# LFO.net
KiCad netlist of a schematic drawn in EAGLE
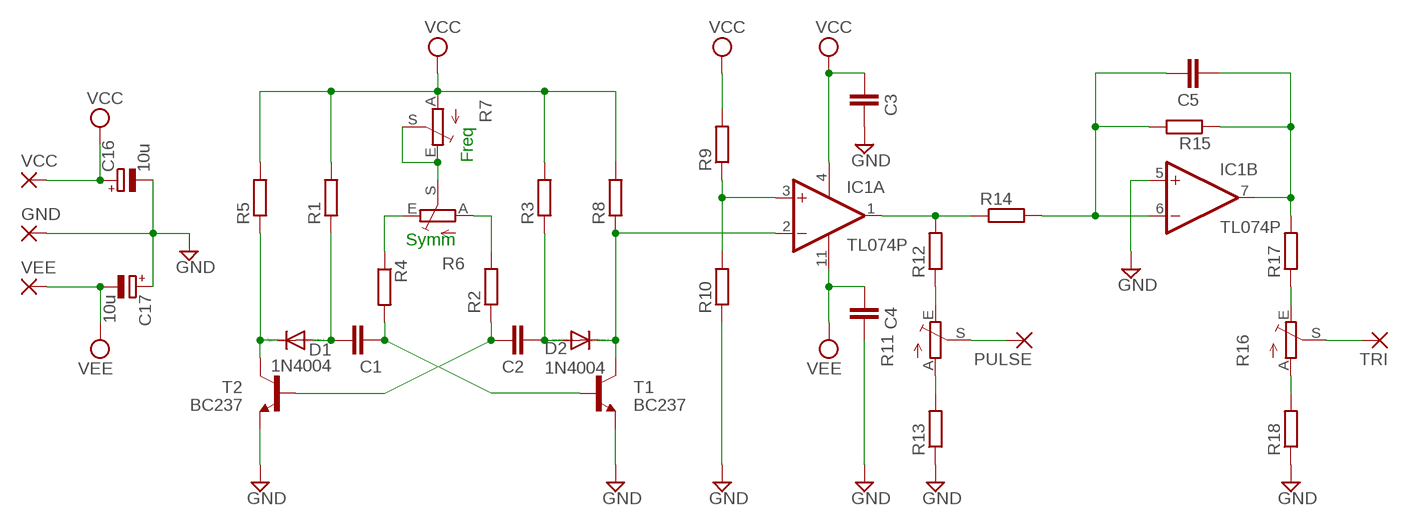
[diagram p0: schematic, sheet 1]

(export (version "E")
  (design (tool "Eeschema 10.0.6"))
  (components
    (comp (ref "C1")
      (value "C-EU050-045X075")
      (footprint "eagle-import:C050-045X075")
      (libsource (lib "eagle-import") (part "C-EU050-045X075"))
    )
    (comp (ref "C2")
      (value "C-EU050-045X075")
      (footprint "eagle-import:C050-045X075")
      (libsource (lib "eagle-import") (part "C-EU050-045X075"))
    )
    (comp (ref "C3")
      (value "C-EU050-045X075")
      (footprint "eagle-import:C050-045X075")
      (libsource (lib "eagle-import") (part "C-EU050-045X075"))
    )
    (comp (ref "C4")
      (value "C-EU050-045X075")
      (footprint "eagle-import:C050-045X075")
      (libsource (lib "eagle-import") (part "C-EU050-045X075"))
    )
    (comp (ref "C5")
      (value "C-EU050-045X075")
      (footprint "eagle-import:C050-045X075")
      (libsource (lib "eagle-import") (part "C-EU050-045X075"))
    )
    (comp (ref "C16")
      (value "10u")
      (footprint "eagle-import:E2,5-7")
      (libsource (lib "eagle-import") (part "CPOL-EUE2.5-7"))
    )
    (comp (ref "C17")
      (value "10u")
      (footprint "eagle-import:E2,5-7")
      (libsource (lib "eagle-import") (part "CPOL-EUE2.5-7"))
    )
    (comp (ref "D1")
      (value "1N4004")
      (footprint "eagle-import:DO41-10")
      (libsource (lib "eagle-import") (part "1N4004"))
    )
    (comp (ref "D2")
      (value "1N4004")
      (footprint "eagle-import:DO41-10")
      (libsource (lib "eagle-import") (part "1N4004"))
    )
    (comp (ref "GND")
      (value "3,17/1,1")
      (footprint "eagle-import:3,17_1,1")
      (libsource (lib "eagle-import") (part "3,17/1,1"))
    )
    (comp (ref "IC1")
      (value "TL074P")
      (footprint "eagle-import:DIL14")
      (libsource (lib "eagle-import") (part "TL074P"))
    )
    (comp (ref "PULSE")
      (value "3,17/1,1")
      (footprint "eagle-import:3,17_1,1")
      (libsource (lib "eagle-import") (part "3,17/1,1"))
    )
    (comp (ref "R1")
      (value "R-EU_0207/10")
      (footprint "eagle-import:0207_10")
      (libsource (lib "eagle-import") (part "R-EU_0207/10"))
    )
    (comp (ref "R2")
      (value "R-EU_0207/10")
      (footprint "eagle-import:0207_10")
      (libsource (lib "eagle-import") (part "R-EU_0207/10"))
    )
    (comp (ref "R3")
      (value "R-EU_0207/10")
      (footprint "eagle-import:0207_10")
      (libsource (lib "eagle-import") (part "R-EU_0207/10"))
    )
    (comp (ref "R4")
      (value "R-EU_0207/10")
      (footprint "eagle-import:0207_10")
      (libsource (lib "eagle-import") (part "R-EU_0207/10"))
    )
    (comp (ref "R5")
      (value "R-EU_0207/10")
      (footprint "eagle-import:0207_10")
      (libsource (lib "eagle-import") (part "R-EU_0207/10"))
    )
    (comp (ref "R6")
      (value "TRIM_EU-S75P")
      (footprint "eagle-import:S75P")
      (libsource (lib "eagle-import") (part "TRIM_EU-S75P"))
    )
    (comp (ref "R7")
      (value "TRIM_EU-S75P")
      (footprint "eagle-import:S75P")
      (libsource (lib "eagle-import") (part "TRIM_EU-S75P"))
    )
    (comp (ref "R8")
      (value "R-EU_0207/10")
      (footprint "eagle-import:0207_10")
      (libsource (lib "eagle-import") (part "R-EU_0207/10"))
    )
    (comp (ref "R9")
      (value "R-EU_0207/10")
      (footprint "eagle-import:0207_10")
      (libsource (lib "eagle-import") (part "R-EU_0207/10"))
    )
    (comp (ref "R10")
      (value "R-EU_0207/10")
      (footprint "eagle-import:0207_10")
      (libsource (lib "eagle-import") (part "R-EU_0207/10"))
    )
    (comp (ref "R11")
      (value "TRIM_EU-S75P")
      (footprint "eagle-import:S75P")
      (libsource (lib "eagle-import") (part "TRIM_EU-S75P"))
    )
    (comp (ref "R12")
      (value "R-EU_0207/10")
      (footprint "eagle-import:0207_10")
      (libsource (lib "eagle-import") (part "R-EU_0207/10"))
    )
    (comp (ref "R13")
      (value "R-EU_0207/10")
      (footprint "eagle-import:0207_10")
      (libsource (lib "eagle-import") (part "R-EU_0207/10"))
    )
    (comp (ref "R14")
      (value "R-EU_0207/10")
      (footprint "eagle-import:0207_10")
      (libsource (lib "eagle-import") (part "R-EU_0207/10"))
    )
    (comp (ref "R15")
      (value "R-EU_0207/10")
      (footprint "eagle-import:0207_10")
      (libsource (lib "eagle-import") (part "R-EU_0207/10"))
    )
    (comp (ref "R16")
      (value "TRIM_EU-S75P")
      (footprint "eagle-import:S75P")
      (libsource (lib "eagle-import") (part "TRIM_EU-S75P"))
    )
    (comp (ref "R17")
      (value "R-EU_0207/10")
      (footprint "eagle-import:0207_10")
      (libsource (lib "eagle-import") (part "R-EU_0207/10"))
    )
    (comp (ref "R18")
      (value "R-EU_0207/10")
      (footprint "eagle-import:0207_10")
      (libsource (lib "eagle-import") (part "R-EU_0207/10"))
    )
    (comp (ref "T1")
      (value "BC237")
      (footprint "eagle-import:TO92")
      (libsource (lib "eagle-import") (part "BC237"))
    )
    (comp (ref "T2")
      (value "BC237")
      (footprint "eagle-import:TO92")
      (libsource (lib "eagle-import") (part "BC237"))
    )
    (comp (ref "TRI")
      (value "3,17/1,1")
      (footprint "eagle-import:3,17_1,1")
      (libsource (lib "eagle-import") (part "3,17/1,1"))
    )
    (comp (ref "VCC")
      (value "3,17/1,1")
      (footprint "eagle-import:3,17_1,1")
      (libsource (lib "eagle-import") (part "3,17/1,1"))
    )
    (comp (ref "VEE")
      (value "3,17/1,1")
      (footprint "eagle-import:3,17_1,1")
      (libsource (lib "eagle-import") (part "3,17/1,1"))
    )
  )
  (nets
    (net (code "1") (name "GND") (class "Default")
      (node (ref "C16") (pin "-") (pinfunction "-_-") (pintype "passive"))
      (node (ref "C17") (pin "+") (pinfunction "+_+") (pintype "passive"))
      (node (ref "C3") (pin "2") (pinfunction "2_2") (pintype "passive"))
      (node (ref "C4") (pin "2") (pinfunction "2_2") (pintype "passive"))
      (node (ref "GND") (pin "1") (pinfunction "P_1") (pintype "passive"))
      (node (ref "IC1") (pin "5") (pinfunction "+IN_5") (pintype "input"))
      (node (ref "R10") (pin "1") (pinfunction "1_1") (pintype "passive"))
      (node (ref "R13") (pin "1") (pinfunction "1_1") (pintype "passive"))
      (node (ref "R18") (pin "1") (pinfunction "1_1") (pintype "passive"))
      (node (ref "T1") (pin "1") (pinfunction "E_1") (pintype "passive"))
      (node (ref "T2") (pin "1") (pinfunction "E_1") (pintype "passive"))
    )
    (net (code "2") (name "Net-(C1-Pad2)") (class "Default")
      (node (ref "C1") (pin "2") (pinfunction "2_2") (pintype "passive"))
      (node (ref "D1") (pin "A") (pinfunction "A_A") (pintype "passive"))
      (node (ref "R1") (pin "1") (pinfunction "1_1") (pintype "passive"))
    )
    (net (code "3") (name "Net-(C2-Pad1)") (class "Default")
      (node (ref "C2") (pin "1") (pinfunction "1_1") (pintype "passive"))
      (node (ref "D2") (pin "A") (pinfunction "A_A") (pintype "passive"))
      (node (ref "R3") (pin "1") (pinfunction "1_1") (pintype "passive"))
    )
    (net (code "4") (name "Net-(IC1A-+IN)") (class "Default")
      (node (ref "IC1") (pin "3") (pinfunction "+IN_3") (pintype "input"))
      (node (ref "R10") (pin "2") (pinfunction "2_2") (pintype "passive"))
      (node (ref "R9") (pin "1") (pinfunction "1_1") (pintype "passive"))
    )
    (net (code "5") (name "Net-(IC1A--IN)") (class "Default")
      (node (ref "D2") (pin "C") (pinfunction "C_C") (pintype "passive"))
      (node (ref "IC1") (pin "2") (pinfunction "-IN_2") (pintype "input"))
      (node (ref "R8") (pin "1") (pinfunction "1_1") (pintype "passive"))
      (node (ref "T1") (pin "3") (pinfunction "C_3") (pintype "passive"))
    )
    (net (code "6") (name "Net-(IC1A-OUT)") (class "Default")
      (node (ref "IC1") (pin "1") (pinfunction "OUT_1") (pintype "output"))
      (node (ref "R12") (pin "2") (pinfunction "2_2") (pintype "passive"))
      (node (ref "R14") (pin "1") (pinfunction "1_1") (pintype "passive"))
    )
    (net (code "7") (name "Net-(IC1B--IN)") (class "Default")
      (node (ref "C5") (pin "2") (pinfunction "2_2") (pintype "passive"))
      (node (ref "IC1") (pin "6") (pinfunction "-IN_6") (pintype "input"))
      (node (ref "R14") (pin "2") (pinfunction "2_2") (pintype "passive"))
      (node (ref "R15") (pin "2") (pinfunction "2_2") (pintype "passive"))
    )
    (net (code "8") (name "Net-(IC1B-OUT)") (class "Default")
      (node (ref "C5") (pin "1") (pinfunction "1_1") (pintype "passive"))
      (node (ref "IC1") (pin "7") (pinfunction "OUT_7") (pintype "output"))
      (node (ref "R15") (pin "1") (pinfunction "1_1") (pintype "passive"))
      (node (ref "R17") (pin "2") (pinfunction "2_2") (pintype "passive"))
    )
    (net (code "9") (name "Net-(PULSE-P)") (class "Default")
      (node (ref "PULSE") (pin "1") (pinfunction "P_1") (pintype "passive"))
      (node (ref "R11") (pin "S") (pinfunction "S_S") (pintype "passive"))
    )
    (net (code "10") (name "Net-(R2-Pad2)") (class "Default")
      (node (ref "R2") (pin "2") (pinfunction "2_2") (pintype "passive"))
      (node (ref "R6") (pin "A") (pinfunction "A_A") (pintype "passive"))
    )
    (net (code "11") (name "Net-(R4-Pad1)") (class "Default")
      (node (ref "R4") (pin "1") (pinfunction "1_1") (pintype "passive"))
      (node (ref "R6") (pin "E") (pinfunction "E_E") (pintype "passive"))
    )
    (net (code "12") (name "Net-(R6-PadS)") (class "Default")
      (node (ref "R6") (pin "S") (pinfunction "S_S") (pintype "passive"))
      (node (ref "R7") (pin "E") (pinfunction "E_E") (pintype "passive"))
      (node (ref "R7") (pin "S") (pinfunction "S_S") (pintype "passive"))
    )
    (net (code "13") (name "Net-(R11-PadA)") (class "Default")
      (node (ref "R11") (pin "A") (pinfunction "A_A") (pintype "passive"))
      (node (ref "R13") (pin "2") (pinfunction "2_2") (pintype "passive"))
    )
    (net (code "14") (name "Net-(R11-PadE)") (class "Default")
      (node (ref "R11") (pin "E") (pinfunction "E_E") (pintype "passive"))
      (node (ref "R12") (pin "1") (pinfunction "1_1") (pintype "passive"))
    )
    (net (code "15") (name "Net-(R16-PadA)") (class "Default")
      (node (ref "R16") (pin "A") (pinfunction "A_A") (pintype "passive"))
      (node (ref "R18") (pin "2") (pinfunction "2_2") (pintype "passive"))
    )
    (net (code "16") (name "Net-(R16-PadE)") (class "Default")
      (node (ref "R16") (pin "E") (pinfunction "E_E") (pintype "passive"))
      (node (ref "R17") (pin "1") (pinfunction "1_1") (pintype "passive"))
    )
    (net (code "17") (name "Net-(T1-B)") (class "Default")
      (node (ref "C1") (pin "1") (pinfunction "1_1") (pintype "passive"))
      (node (ref "R4") (pin "2") (pinfunction "2_2") (pintype "passive"))
      (node (ref "T1") (pin "2") (pinfunction "B_2") (pintype "passive"))
    )
    (net (code "18") (name "Net-(T2-B)") (class "Default")
      (node (ref "C2") (pin "2") (pinfunction "2_2") (pintype "passive"))
      (node (ref "R2") (pin "1") (pinfunction "1_1") (pintype "passive"))
      (node (ref "T2") (pin "2") (pinfunction "B_2") (pintype "passive"))
    )
    (net (code "19") (name "Net-(T2-C)") (class "Default")
      (node (ref "D1") (pin "C") (pinfunction "C_C") (pintype "passive"))
      (node (ref "R5") (pin "1") (pinfunction "1_1") (pintype "passive"))
      (node (ref "T2") (pin "3") (pinfunction "C_3") (pintype "passive"))
    )
    (net (code "20") (name "Net-(TRI-P)") (class "Default")
      (node (ref "R16") (pin "S") (pinfunction "S_S") (pintype "passive"))
      (node (ref "TRI") (pin "1") (pinfunction "P_1") (pintype "passive"))
    )
    (net (code "21") (name "VCC") (class "Default")
      (node (ref "C16") (pin "+") (pinfunction "+_+") (pintype "passive"))
      (node (ref "C3") (pin "1") (pinfunction "1_1") (pintype "passive"))
      (node (ref "IC1") (pin "4") (pinfunction "V+_4") (pintype "power_in"))
      (node (ref "R1") (pin "2") (pinfunction "2_2") (pintype "passive"))
      (node (ref "R3") (pin "2") (pinfunction "2_2") (pintype "passive"))
      (node (ref "R5") (pin "2") (pinfunction "2_2") (pintype "passive"))
      (node (ref "R7") (pin "A") (pinfunction "A_A") (pintype "passive"))
      (node (ref "R8") (pin "2") (pinfunction "2_2") (pintype "passive"))
      (node (ref "R9") (pin "2") (pinfunction "2_2") (pintype "passive"))
      (node (ref "VCC") (pin "1") (pinfunction "P_1") (pintype "passive"))
    )
    (net (code "22") (name "VEE") (class "Default")
      (node (ref "C17") (pin "-") (pinfunction "-_-") (pintype "passive"))
      (node (ref "C4") (pin "1") (pinfunction "1_1") (pintype "passive"))
      (node (ref "IC1") (pin "11") (pinfunction "V-_11") (pintype "power_in"))
      (node (ref "VEE") (pin "1") (pinfunction "P_1") (pintype "passive"))
    )
  )
)
